# 555.net
KiCad netlist of a schematic drawn in EAGLE
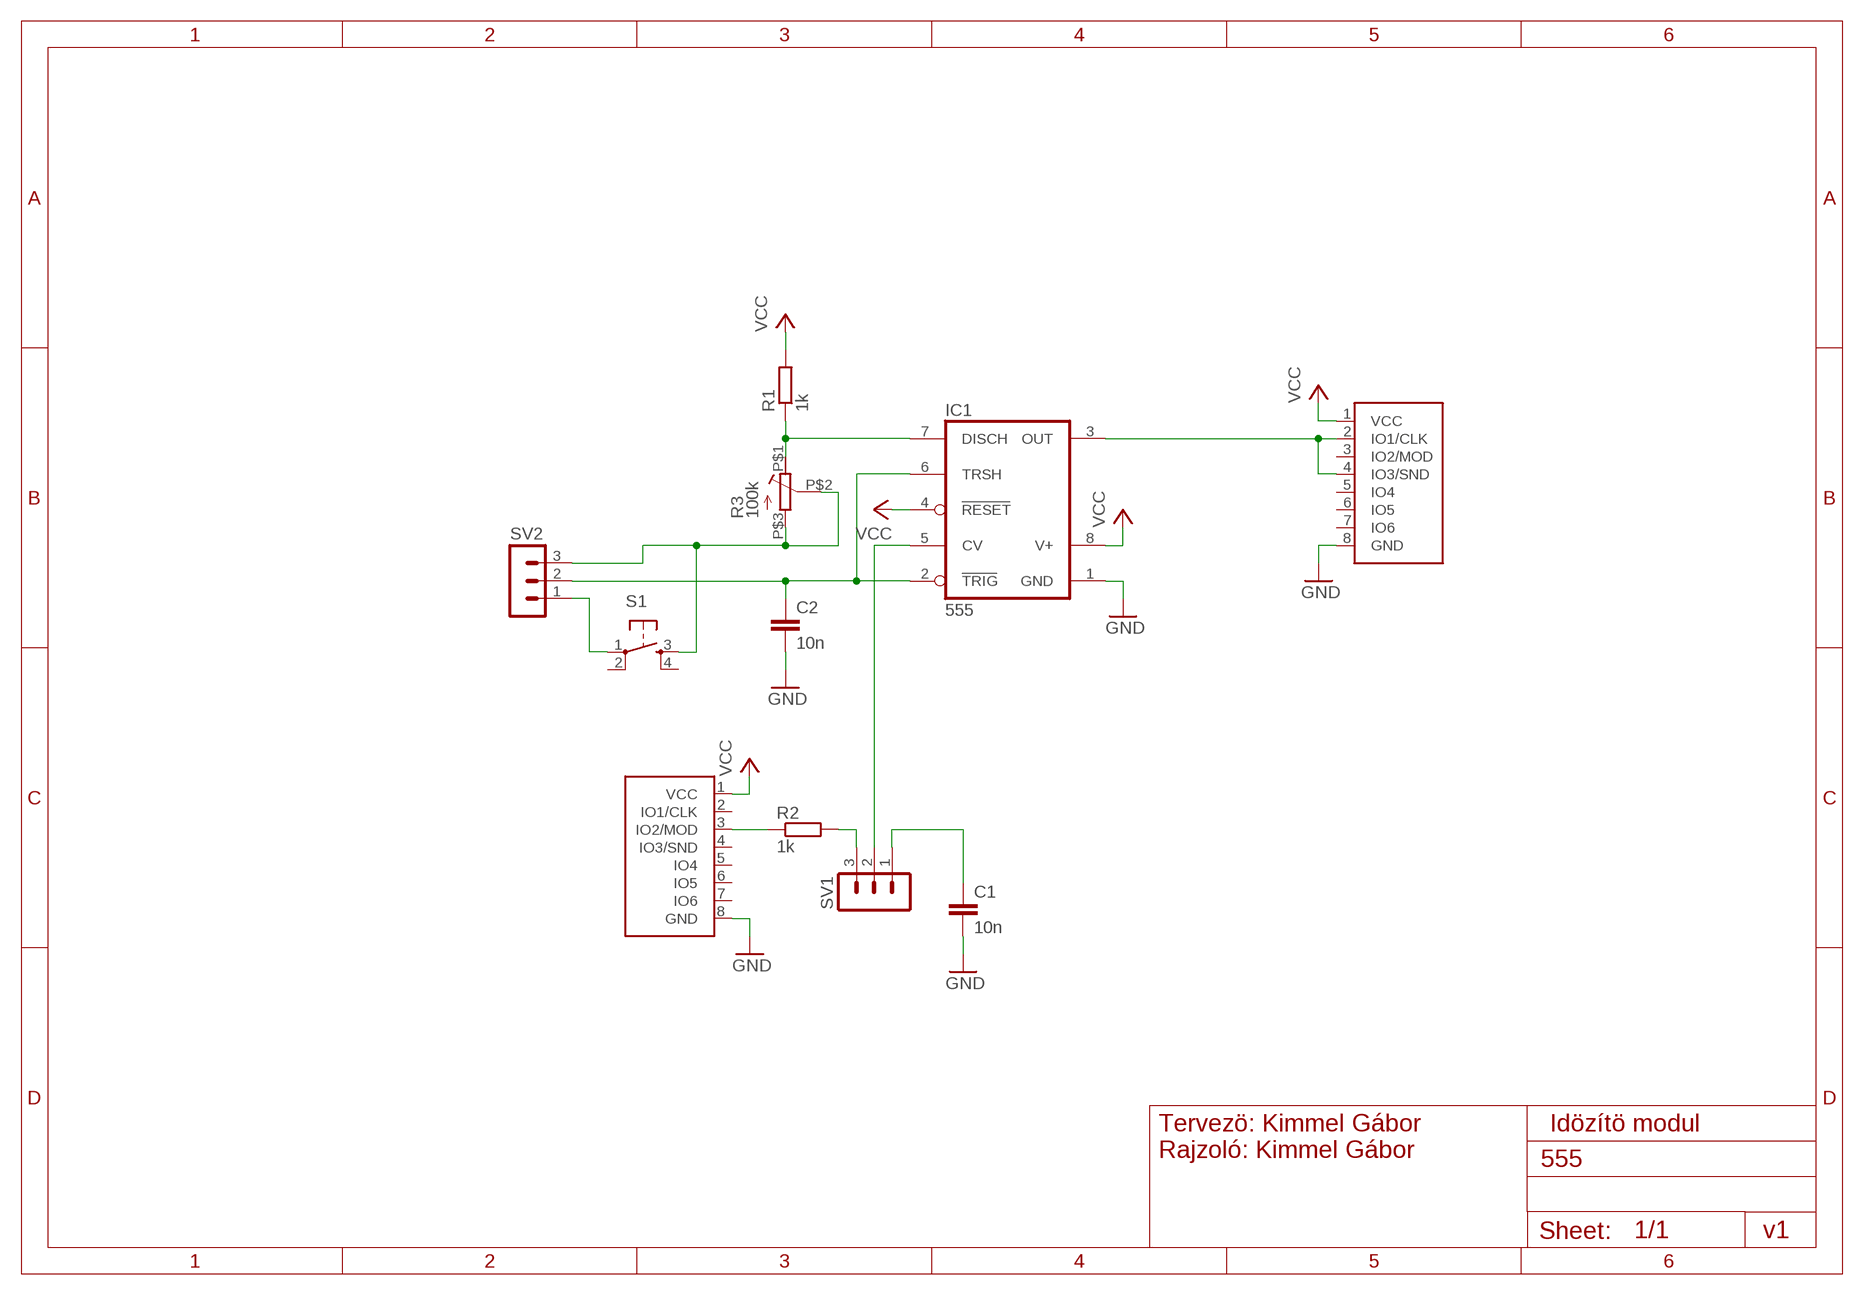
[diagram p0: schematic, sheet 1]

(export (version "E")
  (design (tool "Eeschema 10.0.6"))
  (components
    (comp (ref "C1")
      (value "10n")
      (footprint "eagle-import:C075-032X103")
      (libsource (lib "eagle-import") (part "C-EU075-032X103"))
    )
    (comp (ref "C2")
      (value "10n")
      (footprint "eagle-import:C075-032X103")
      (libsource (lib "eagle-import") (part "C-EU075-032X103"))
    )
    (comp (ref "IC1")
      (value "555")
      (footprint "eagle-import:DIL08")
      (fields (field (name "MF") "MAXIM") (field (name "MPN") "ICM7555IPA+"))
      (libsource (lib "eagle-import") (part "ICM7555"))
    )
    (comp (ref "R1")
      (value "1k")
      (footprint "eagle-import:0309_12")
      (libsource (lib "eagle-import") (part "R-EU_0309/12"))
    )
    (comp (ref "R2")
      (value "1k")
      (footprint "eagle-import:0309_12")
      (libsource (lib "eagle-import") (part "R-EU_0309/12"))
    )
    (comp (ref "R3")
      (value "100k")
      (footprint "eagle-import:GANZ_POT")
      (libsource (lib "eagle-import") (part "GANZ_POTI"))
    )
    (comp (ref "S1")
      (value "TAC_SWITCHPTH")
      (footprint "eagle-import:TACTILE-PTH")
      (libsource (lib "eagle-import") (part "TAC_SWITCHPTH"))
    )
    (comp (ref "SV1")
      (value "MA03-1")
      (footprint "eagle-import:MA03-1")
      (libsource (lib "eagle-import") (part "MA03-1"))
    )
    (comp (ref "SV2")
      (value "MA03-1")
      (footprint "eagle-import:MA03-1")
      (libsource (lib "eagle-import") (part "MA03-1"))
    )
    (comp (ref "U$2")
      (value "ó")
      (footprint "eagle-import:FE08W")
      (libsource (lib "eagle-import") (part "GANZ-CONNECTOR"))
    )
    (comp (ref "U$3")
      (value "GANZ-CONNECTOR-OUT")
      (footprint "eagle-import:MA08-1W")
      (libsource (lib "eagle-import") (part "GANZ-CONNECTOR-OUT"))
    )
  )
  (nets
    (net (code "1") (name "GND") (class "Default")
      (node (ref "C1") (pin "2") (pinfunction "2_2") (pintype "passive"))
      (node (ref "C2") (pin "2") (pinfunction "2_2") (pintype "passive"))
      (node (ref "IC1") (pin "1") (pinfunction "GND_1") (pintype "power_in"))
      (node (ref "U$2") (pin "8") (pinfunction "GND_8") (pintype "bidirectional"))
      (node (ref "U$3") (pin "8") (pinfunction "GND_8") (pintype "bidirectional"))
    )
    (net (code "2") (name "Net-(C1-Pad1)") (class "Default")
      (node (ref "C1") (pin "1") (pinfunction "1_1") (pintype "passive"))
      (node (ref "SV1") (pin "1") (pinfunction "1_1") (pintype "passive"))
    )
    (net (code "3") (name "Net-(IC1-CV)") (class "Default")
      (node (ref "IC1") (pin "5") (pinfunction "CV_5") (pintype "passive"))
      (node (ref "SV1") (pin "2") (pinfunction "2_2") (pintype "passive"))
    )
    (net (code "4") (name "Net-(IC1-DISCH)") (class "Default")
      (node (ref "IC1") (pin "7") (pinfunction "DISCH_7") (pintype "input"))
      (node (ref "R1") (pin "1") (pinfunction "1_1") (pintype "passive"))
      (node (ref "R3") (pin "P$1") (pinfunction "A_P$1") (pintype "passive"))
    )
    (net (code "5") (name "Net-(IC1-OUT)") (class "Default")
      (node (ref "IC1") (pin "3") (pinfunction "OUT_3") (pintype "output"))
      (node (ref "U$3") (pin "2") (pinfunction "IO1/CLK_2") (pintype "bidirectional"))
      (node (ref "U$3") (pin "4") (pinfunction "IO3/SND_4") (pintype "bidirectional"))
    )
    (net (code "6") (name "Net-(IC1-TRIG)") (class "Default")
      (node (ref "C2") (pin "1") (pinfunction "1_1") (pintype "passive"))
      (node (ref "IC1") (pin "2") (pinfunction "TRIG_2") (pintype "bidirectional"))
      (node (ref "IC1") (pin "6") (pinfunction "TRSH_6") (pintype "input"))
      (node (ref "SV2") (pin "2") (pinfunction "2_2") (pintype "passive"))
    )
    (net (code "7") (name "Net-(R2-Pad2)") (class "Default")
      (node (ref "R2") (pin "2") (pinfunction "2_2") (pintype "passive"))
      (node (ref "SV1") (pin "3") (pinfunction "3_3") (pintype "passive"))
    )
    (net (code "8") (name "Net-(R3-E)") (class "Default")
      (node (ref "R3") (pin "P$2") (pinfunction "S_P$2") (pintype "passive"))
      (node (ref "R3") (pin "P$3") (pinfunction "E_P$3") (pintype "passive"))
      (node (ref "S1") (pin "3") (pinfunction "3_3") (pintype "passive"))
      (node (ref "SV2") (pin "3") (pinfunction "3_3") (pintype "passive"))
    )
    (net (code "9") (name "Net-(S1-Pad1)") (class "Default")
      (node (ref "S1") (pin "1") (pinfunction "1_1") (pintype "passive"))
      (node (ref "SV2") (pin "1") (pinfunction "1_1") (pintype "passive"))
    )
    (net (code "10") (name "Net-(U$2-IO2{slash}MOD)") (class "Default")
      (node (ref "R2") (pin "1") (pinfunction "1_1") (pintype "passive"))
      (node (ref "U$2") (pin "3") (pinfunction "IO2/MOD_3") (pintype "bidirectional"))
    )
    (net (code "11") (name "VCC") (class "Default")
      (node (ref "IC1") (pin "4") (pinfunction "RESET_4") (pintype "input"))
      (node (ref "IC1") (pin "8") (pinfunction "V+_8") (pintype "power_in"))
      (node (ref "R1") (pin "2") (pinfunction "2_2") (pintype "passive"))
      (node (ref "U$2") (pin "1") (pinfunction "VCC_1") (pintype "bidirectional"))
      (node (ref "U$3") (pin "1") (pinfunction "VCC_1") (pintype "bidirectional"))
    )
    (net (code "12") (name "unconnected-(S1-Pad2)") (class "Default")
      (node (ref "S1") (pin "2") (pinfunction "2_2") (pintype "passive"))
    )
    (net (code "13") (name "unconnected-(S1-Pad4)") (class "Default")
      (node (ref "S1") (pin "4") (pinfunction "4_4") (pintype "passive"))
    )
    (net (code "14") (name "unconnected-(U$2-IO1{slash}CLK-Pad2)") (class "Default")
      (node (ref "U$2") (pin "2") (pinfunction "IO1/CLK_2") (pintype "bidirectional"))
    )
    (net (code "15") (name "unconnected-(U$2-IO3{slash}SND-Pad4)") (class "Default")
      (node (ref "U$2") (pin "4") (pinfunction "IO3/SND_4") (pintype "bidirectional"))
    )
    (net (code "16") (name "unconnected-(U$2-IO4-Pad5)") (class "Default")
      (node (ref "U$2") (pin "5") (pinfunction "IO4_5") (pintype "bidirectional"))
    )
    (net (code "17") (name "unconnected-(U$2-IO5-Pad6)") (class "Default")
      (node (ref "U$2") (pin "6") (pinfunction "IO5_6") (pintype "bidirectional"))
    )
    (net (code "18") (name "unconnected-(U$2-IO6-Pad7)") (class "Default")
      (node (ref "U$2") (pin "7") (pinfunction "IO6_7") (pintype "bidirectional"))
    )
    (net (code "19") (name "unconnected-(U$3-IO2{slash}MOD-Pad3)") (class "Default")
      (node (ref "U$3") (pin "3") (pinfunction "IO2/MOD_3") (pintype "bidirectional"))
    )
    (net (code "20") (name "unconnected-(U$3-IO4-Pad5)") (class "Default")
      (node (ref "U$3") (pin "5") (pinfunction "IO4_5") (pintype "bidirectional"))
    )
    (net (code "21") (name "unconnected-(U$3-IO5-Pad6)") (class "Default")
      (node (ref "U$3") (pin "6") (pinfunction "IO5_6") (pintype "bidirectional"))
    )
    (net (code "22") (name "unconnected-(U$3-IO6-Pad7)") (class "Default")
      (node (ref "U$3") (pin "7") (pinfunction "IO6_7") (pintype "bidirectional"))
    )
  )
)
